# untitled.net
KiCad netlist of a schematic drawn in EAGLE
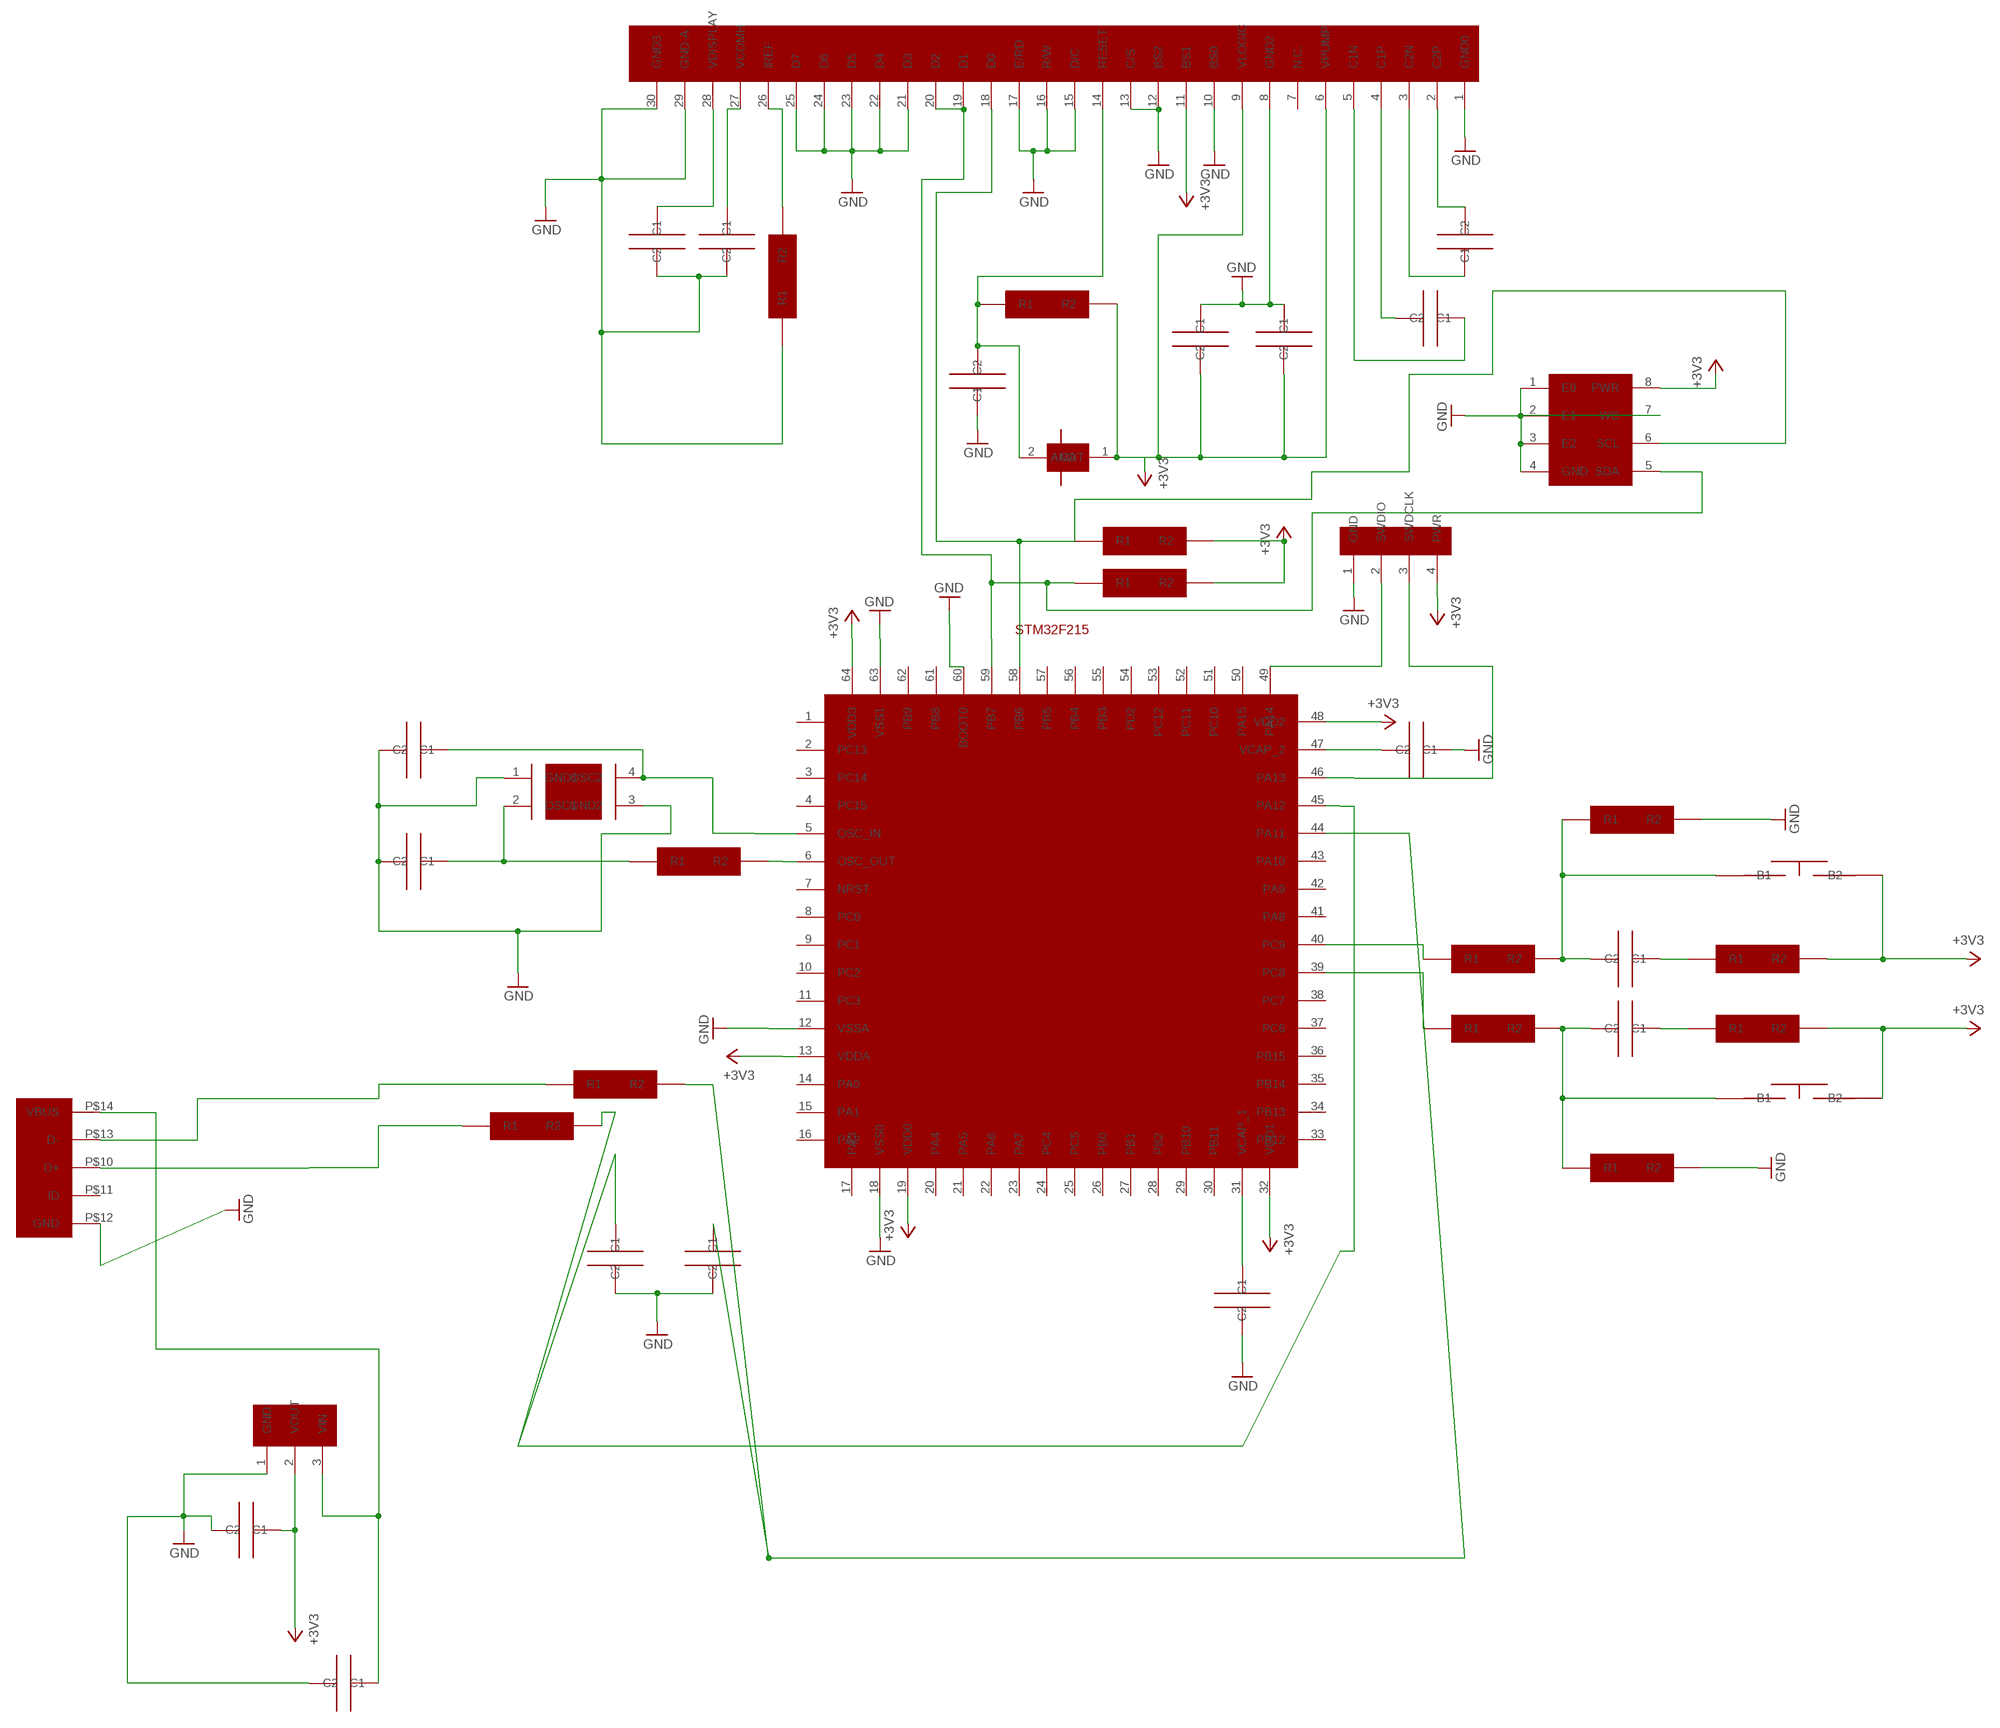
[diagram p0: schematic, sheet 1]

(export (version "E")
  (design (tool "Eeschema 10.0.6"))
  (components
    (comp (ref "C3")
      (value "10мкф")
      (footprint "eagle-import:0805")
      (libsource (lib "eagle-import") (part "C0805"))
    )
    (comp (ref "C4")
      (value "22мкф")
      (footprint "eagle-import:0805")
      (libsource (lib "eagle-import") (part "C0805"))
    )
    (comp (ref "C10")
      (value "100нф")
      (footprint "eagle-import:0805")
      (libsource (lib "eagle-import") (part "C0805"))
    )
    (comp (ref "C11")
      (value "100нф")
      (footprint "eagle-import:0805")
      (libsource (lib "eagle-import") (part "C0805"))
    )
    (comp (ref "C28")
      (value "8пф")
      (footprint "eagle-import:0805")
      (libsource (lib "eagle-import") (part "C0805"))
    )
    (comp (ref "C29")
      (value "8пф")
      (footprint "eagle-import:0805")
      (libsource (lib "eagle-import") (part "C0805"))
    )
    (comp (ref "C30")
      (value "47пф")
      (footprint "eagle-import:0805")
      (libsource (lib "eagle-import") (part "C0805"))
    )
    (comp (ref "C31")
      (value "47пф")
      (footprint "eagle-import:0805")
      (libsource (lib "eagle-import") (part "C0805"))
    )
    (comp (ref "C36")
      (value "2.2мкф")
      (footprint "eagle-import:0805")
      (libsource (lib "eagle-import") (part "C0805"))
    )
    (comp (ref "C37")
      (value "2.2мкф")
      (footprint "eagle-import:0805")
      (libsource (lib "eagle-import") (part "C0805"))
    )
    (comp (ref "C39")
      (value "1мкф")
      (footprint "eagle-import:0805")
      (libsource (lib "eagle-import") (part "C0805"))
    )
    (comp (ref "C40")
      (value "1мкф")
      (footprint "eagle-import:0805")
      (libsource (lib "eagle-import") (part "C0805"))
    )
    (comp (ref "C41")
      (value "1мкф")
      (footprint "eagle-import:0805")
      (libsource (lib "eagle-import") (part "C0805"))
    )
    (comp (ref "C42")
      (value "1мкф")
      (footprint "eagle-import:0805")
      (libsource (lib "eagle-import") (part "C0805"))
    )
    (comp (ref "C44")
      (value "4.7мкф")
      (footprint "eagle-import:0805")
      (libsource (lib "eagle-import") (part "C0805"))
    )
    (comp (ref "C46")
      (value "2.2мкф")
      (footprint "eagle-import:0805")
      (libsource (lib "eagle-import") (part "C0805"))
    )
    (comp (ref "C47")
      (value "4.7мкф")
      (footprint "eagle-import:0805")
      (libsource (lib "eagle-import") (part "C0805"))
    )
    (comp (ref "R2")
      (value "330")
      (footprint "eagle-import:0805")
      (libsource (lib "eagle-import") (part "R0805"))
    )
    (comp (ref "R3")
      (value "330")
      (footprint "eagle-import:0805")
      (libsource (lib "eagle-import") (part "R0805"))
    )
    (comp (ref "R6")
      (value "100")
      (footprint "eagle-import:0805")
      (libsource (lib "eagle-import") (part "R0805"))
    )
    (comp (ref "R7")
      (value "100")
      (footprint "eagle-import:0805")
      (libsource (lib "eagle-import") (part "R0805"))
    )
    (comp (ref "R8")
      (value "10к")
      (footprint "eagle-import:0805")
      (libsource (lib "eagle-import") (part "R0805"))
    )
    (comp (ref "R9")
      (value "10к")
      (footprint "eagle-import:0805")
      (libsource (lib "eagle-import") (part "R0805"))
    )
    (comp (ref "R14")
      (value "220k")
      (footprint "eagle-import:0805")
      (libsource (lib "eagle-import") (part "R0805"))
    )
    (comp (ref "R15")
      (value "220k")
      (footprint "eagle-import:0805")
      (libsource (lib "eagle-import") (part "R0805"))
    )
    (comp (ref "R32")
      (value "820")
      (footprint "eagle-import:0805")
      (libsource (lib "eagle-import") (part "R0805"))
    )
    (comp (ref "R33")
      (value "22")
      (footprint "eagle-import:0805")
      (libsource (lib "eagle-import") (part "R0805"))
    )
    (comp (ref "R34")
      (value "22")
      (footprint "eagle-import:0805")
      (libsource (lib "eagle-import") (part "R0805"))
    )
    (comp (ref "R43")
      (value "4.7к")
      (footprint "eagle-import:0805")
      (libsource (lib "eagle-import") (part "R0805"))
    )
    (comp (ref "R48")
      (value "910к")
      (footprint "eagle-import:0805")
      (libsource (lib "eagle-import") (part "R0805"))
    )
    (comp (ref "U$1")
      (value "STM32F215RESTM32")
      (footprint "eagle-import:QFP50P1300X1300X120-64N")
      (libsource (lib "eagle-import") (part "STM32F215RESTM32"))
    )
    (comp (ref "U$2")
      (value "AMS1117")
      (footprint "eagle-import:SOT229P729X180-4N")
      (libsource (lib "eagle-import") (part "AMS1117"))
    )
    (comp (ref "U$3")
      (value "I2CMEMORY")
      (footprint "eagle-import:SOIC127P600X175-8N")
      (libsource (lib "eagle-import") (part "I2CMEMORY"))
    )
    (comp (ref "U$4")
      (value "USBUSBT")
      (footprint "eagle-import:USBT")
      (libsource (lib "eagle-import") (part "USBUSBT"))
    )
    (comp (ref "U$5")
      (value "SWDSWDD")
      (footprint "eagle-import:HDRV4W64P254_1X4_1016X508X838B")
      (libsource (lib "eagle-import") (part "SWDSWDD"))
    )
    (comp (ref "U$18")
      (value "BUTTON")
      (footprint "eagle-import:BUTTON")
      (libsource (lib "eagle-import") (part "BUTTON"))
    )
    (comp (ref "U$19")
      (value "BUTTON")
      (footprint "eagle-import:BUTTON")
      (libsource (lib "eagle-import") (part "BUTTON"))
    )
    (comp (ref "U$26")
      (value "NX2520SA")
      (footprint "eagle-import:NX2520SA")
      (libsource (lib "eagle-import") (part "NX2520SA"))
    )
    (comp (ref "U$38")
      (value "SSD1306")
      (footprint "eagle-import:SSD1306")
      (libsource (lib "eagle-import") (part "SSD1306"))
    )
    (comp (ref "U$45")
      (value "ESD")
      (footprint "eagle-import:ESD")
      (libsource (lib "eagle-import") (part "ESD"))
    )
  )
  (nets
    (net (code "1") (name "+3V3") (class "Default")
      (node (ref "C4") (pin "2") (pinfunction "C2_2") (pintype "bidirectional"))
      (node (ref "C41") (pin "1") (pinfunction "C1_1") (pintype "bidirectional"))
      (node (ref "C42") (pin "1") (pinfunction "C1_1") (pintype "bidirectional"))
      (node (ref "R43") (pin "2") (pinfunction "R2_2") (pintype "bidirectional"))
      (node (ref "R6") (pin "2") (pinfunction "R2_2") (pintype "bidirectional"))
      (node (ref "R7") (pin "2") (pinfunction "R2_2") (pintype "bidirectional"))
      (node (ref "R8") (pin "2") (pinfunction "R2_2") (pintype "bidirectional"))
      (node (ref "R9") (pin "2") (pinfunction "R2_2") (pintype "bidirectional"))
      (node (ref "U$1") (pin "13") (pinfunction "VDDA_13") (pintype "bidirectional"))
      (node (ref "U$1") (pin "19") (pinfunction "VDD0_19") (pintype "bidirectional"))
      (node (ref "U$1") (pin "32") (pinfunction "VDD1_32") (pintype "power_in"))
      (node (ref "U$1") (pin "48") (pinfunction "VDD2_48") (pintype "bidirectional"))
      (node (ref "U$1") (pin "64") (pinfunction "VDD3_64") (pintype "bidirectional"))
      (node (ref "U$18") (pin "2") (pinfunction "B2_2") (pintype "bidirectional"))
      (node (ref "U$19") (pin "2") (pinfunction "B2_2") (pintype "bidirectional"))
      (node (ref "U$2") (pin "2") (pinfunction "VOUT_2") (pintype "bidirectional"))
      (node (ref "U$3") (pin "8") (pinfunction "PWR_8") (pintype "bidirectional"))
      (node (ref "U$38") (pin "11") (pinfunction "BS1_11") (pintype "bidirectional"))
      (node (ref "U$38") (pin "6") (pinfunction "VPUMP_6") (pintype "bidirectional"))
      (node (ref "U$38") (pin "9") (pinfunction "VLOGIC_9") (pintype "bidirectional"))
      (node (ref "U$45") (pin "1") (pinfunction "ANO_1") (pintype "bidirectional"))
      (node (ref "U$5") (pin "4") (pinfunction "PWR_4") (pintype "bidirectional"))
    )
    (net (code "2") (name "/VBAT") (class "Default")
      (node (ref "U$1") (pin "1") (pinfunction "VBAT_1") (pintype "power_in"))
    )
    (net (code "3") (name "GND") (class "Default")
      (node (ref "C28") (pin "1") (pinfunction "C1_1") (pintype "bidirectional"))
      (node (ref "C29") (pin "1") (pinfunction "C1_1") (pintype "bidirectional"))
      (node (ref "C3") (pin "1") (pinfunction "C1_1") (pintype "bidirectional"))
      (node (ref "C30") (pin "1") (pinfunction "C1_1") (pintype "bidirectional"))
      (node (ref "C31") (pin "1") (pinfunction "C1_1") (pintype "bidirectional"))
      (node (ref "C36") (pin "1") (pinfunction "C1_1") (pintype "bidirectional"))
      (node (ref "C37") (pin "2") (pinfunction "C2_2") (pintype "bidirectional"))
      (node (ref "C4") (pin "1") (pinfunction "C1_1") (pintype "bidirectional"))
      (node (ref "C41") (pin "2") (pinfunction "C2_2") (pintype "bidirectional"))
      (node (ref "C42") (pin "2") (pinfunction "C2_2") (pintype "bidirectional"))
      (node (ref "C44") (pin "2") (pinfunction "C2_2") (pintype "bidirectional"))
      (node (ref "C46") (pin "1") (pinfunction "C1_1") (pintype "bidirectional"))
      (node (ref "C47") (pin "1") (pinfunction "C1_1") (pintype "bidirectional"))
      (node (ref "R14") (pin "2") (pinfunction "R2_2") (pintype "bidirectional"))
      (node (ref "R15") (pin "2") (pinfunction "R2_2") (pintype "bidirectional"))
      (node (ref "R48") (pin "1") (pinfunction "R1_1") (pintype "bidirectional"))
      (node (ref "U$1") (pin "12") (pinfunction "VSSA_12") (pintype "bidirectional"))
      (node (ref "U$1") (pin "18") (pinfunction "VSS0_18") (pintype "bidirectional"))
      (node (ref "U$1") (pin "60") (pinfunction "BOOT0_60") (pintype "bidirectional"))
      (node (ref "U$1") (pin "63") (pinfunction "VSS1_63") (pintype "bidirectional"))
      (node (ref "U$2") (pin "1") (pinfunction "GND_1") (pintype "bidirectional"))
      (node (ref "U$26") (pin "1") (pinfunction "GND1_1") (pintype "bidirectional"))
      (node (ref "U$26") (pin "3") (pinfunction "GND2_3") (pintype "bidirectional"))
      (node (ref "U$3") (pin "1") (pinfunction "E0_1") (pintype "bidirectional"))
      (node (ref "U$3") (pin "2") (pinfunction "E1_2") (pintype "bidirectional"))
      (node (ref "U$3") (pin "3") (pinfunction "E2_3") (pintype "bidirectional"))
      (node (ref "U$3") (pin "4") (pinfunction "GND_4") (pintype "bidirectional"))
      (node (ref "U$3") (pin "7") (pinfunction "WC_7") (pintype "bidirectional"))
      (node (ref "U$38") (pin "1") (pinfunction "GND0_1") (pintype "bidirectional"))
      (node (ref "U$38") (pin "10") (pinfunction "BS0_10") (pintype "bidirectional"))
      (node (ref "U$38") (pin "12") (pinfunction "BS2_12") (pintype "bidirectional"))
      (node (ref "U$38") (pin "13") (pinfunction "C/S_13") (pintype "bidirectional"))
      (node (ref "U$38") (pin "15") (pinfunction "D/C_15") (pintype "bidirectional"))
      (node (ref "U$38") (pin "16") (pinfunction "R/W_16") (pintype "bidirectional"))
      (node (ref "U$38") (pin "17") (pinfunction "E/RD_17") (pintype "bidirectional"))
      (node (ref "U$38") (pin "21") (pinfunction "D3_21") (pintype "bidirectional"))
      (node (ref "U$38") (pin "22") (pinfunction "D4_22") (pintype "bidirectional"))
      (node (ref "U$38") (pin "23") (pinfunction "D5_23") (pintype "bidirectional"))
      (node (ref "U$38") (pin "24") (pinfunction "D6_24") (pintype "bidirectional"))
      (node (ref "U$38") (pin "25") (pinfunction "D7_25") (pintype "bidirectional"))
      (node (ref "U$38") (pin "29") (pinfunction "GND-A_29") (pintype "bidirectional"))
      (node (ref "U$38") (pin "30") (pinfunction "GND3_30") (pintype "bidirectional"))
      (node (ref "U$38") (pin "8") (pinfunction "GND2_8") (pintype "bidirectional"))
      (node (ref "U$4") (pin "P$12") (pinfunction "GND_P$12") (pintype "bidirectional"))
      (node (ref "U$5") (pin "1") (pinfunction "GND_1") (pintype "bidirectional"))
    )
    (net (code "4") (name "Net-(C3-C2)") (class "Default")
      (node (ref "C3") (pin "2") (pinfunction "C2_2") (pintype "bidirectional"))
      (node (ref "U$2") (pin "3") (pinfunction "VIN_3") (pintype "bidirectional"))
      (node (ref "U$4") (pin "P$14") (pinfunction "VBUS_P$14") (pintype "bidirectional"))
    )
    (net (code "5") (name "Net-(C10-C1)") (class "Default")
      (node (ref "C10") (pin "1") (pinfunction "C1_1") (pintype "bidirectional"))
      (node (ref "R14") (pin "1") (pinfunction "R1_1") (pintype "bidirectional"))
      (node (ref "R2") (pin "2") (pinfunction "R2_2") (pintype "bidirectional"))
      (node (ref "U$18") (pin "1") (pinfunction "B1_1") (pintype "bidirectional"))
    )
    (net (code "6") (name "Net-(C10-C2)") (class "Default")
      (node (ref "C10") (pin "2") (pinfunction "C2_2") (pintype "bidirectional"))
      (node (ref "R6") (pin "1") (pinfunction "R1_1") (pintype "bidirectional"))
    )
    (net (code "7") (name "Net-(C11-C1)") (class "Default")
      (node (ref "C11") (pin "1") (pinfunction "C1_1") (pintype "bidirectional"))
      (node (ref "R15") (pin "1") (pinfunction "R1_1") (pintype "bidirectional"))
      (node (ref "R3") (pin "2") (pinfunction "R2_2") (pintype "bidirectional"))
      (node (ref "U$19") (pin "1") (pinfunction "B1_1") (pintype "bidirectional"))
    )
    (net (code "8") (name "Net-(C11-C2)") (class "Default")
      (node (ref "C11") (pin "2") (pinfunction "C2_2") (pintype "bidirectional"))
      (node (ref "R7") (pin "1") (pinfunction "R1_1") (pintype "bidirectional"))
    )
    (net (code "9") (name "Net-(C28-C2)") (class "Default")
      (node (ref "C28") (pin "2") (pinfunction "C2_2") (pintype "bidirectional"))
      (node (ref "U$1") (pin "5") (pinfunction "OSC_IN_5") (pintype "input"))
      (node (ref "U$26") (pin "4") (pinfunction "OSC2_4") (pintype "bidirectional"))
    )
    (net (code "10") (name "Net-(C29-C2)") (class "Default")
      (node (ref "C29") (pin "2") (pinfunction "C2_2") (pintype "bidirectional"))
      (node (ref "R32") (pin "1") (pinfunction "R1_1") (pintype "bidirectional"))
      (node (ref "U$26") (pin "2") (pinfunction "OSC1_2") (pintype "bidirectional"))
    )
    (net (code "11") (name "Net-(C30-C2)") (class "Default")
      (node (ref "C30") (pin "2") (pinfunction "C2_2") (pintype "bidirectional"))
      (node (ref "R33") (pin "2") (pinfunction "R2_2") (pintype "bidirectional"))
      (node (ref "U$1") (pin "44") (pinfunction "PA11_44") (pintype "bidirectional"))
    )
    (net (code "12") (name "Net-(C31-C2)") (class "Default")
      (node (ref "C31") (pin "2") (pinfunction "C2_2") (pintype "bidirectional"))
      (node (ref "R34") (pin "2") (pinfunction "R2_2") (pintype "bidirectional"))
      (node (ref "U$1") (pin "45") (pinfunction "PA12_45") (pintype "bidirectional"))
    )
    (net (code "13") (name "Net-(C36-C2)") (class "Default")
      (node (ref "C36") (pin "2") (pinfunction "C2_2") (pintype "bidirectional"))
      (node (ref "U$1") (pin "31") (pinfunction "VCAP_1_31") (pintype "bidirectional"))
    )
    (net (code "14") (name "Net-(C37-C1)") (class "Default")
      (node (ref "C37") (pin "1") (pinfunction "C1_1") (pintype "bidirectional"))
      (node (ref "U$1") (pin "47") (pinfunction "VCAP_2_47") (pintype "bidirectional"))
    )
    (net (code "15") (name "Net-(C39-C1)") (class "Default")
      (node (ref "C39") (pin "1") (pinfunction "C1_1") (pintype "bidirectional"))
      (node (ref "U$38") (pin "2") (pinfunction "C2P_2") (pintype "bidirectional"))
    )
    (net (code "16") (name "Net-(C39-C2)") (class "Default")
      (node (ref "C39") (pin "2") (pinfunction "C2_2") (pintype "bidirectional"))
      (node (ref "U$38") (pin "3") (pinfunction "C2N_3") (pintype "bidirectional"))
    )
    (net (code "17") (name "Net-(C40-C1)") (class "Default")
      (node (ref "C40") (pin "1") (pinfunction "C1_1") (pintype "bidirectional"))
      (node (ref "U$38") (pin "4") (pinfunction "C1P_4") (pintype "bidirectional"))
    )
    (net (code "18") (name "Net-(C40-C2)") (class "Default")
      (node (ref "C40") (pin "2") (pinfunction "C2_2") (pintype "bidirectional"))
      (node (ref "U$38") (pin "5") (pinfunction "C1N_5") (pintype "bidirectional"))
    )
    (net (code "19") (name "Net-(C44-C1)") (class "Default")
      (node (ref "C44") (pin "1") (pinfunction "C1_1") (pintype "bidirectional"))
      (node (ref "R43") (pin "1") (pinfunction "R1_1") (pintype "bidirectional"))
      (node (ref "U$38") (pin "14") (pinfunction "RESET_14") (pintype "bidirectional"))
      (node (ref "U$45") (pin "2") (pinfunction "CAT_2") (pintype "bidirectional"))
    )
    (net (code "20") (name "Net-(C46-C2)") (class "Default")
      (node (ref "C46") (pin "2") (pinfunction "C2_2") (pintype "bidirectional"))
      (node (ref "U$38") (pin "28") (pinfunction "VDISPLAY_28") (pintype "bidirectional"))
    )
    (net (code "21") (name "Net-(C47-C2)") (class "Default")
      (node (ref "C47") (pin "2") (pinfunction "C2_2") (pintype "bidirectional"))
      (node (ref "U$38") (pin "27") (pinfunction "VCOMH_27") (pintype "bidirectional"))
    )
    (net (code "22") (name "Net-(R2-R1)") (class "Default")
      (node (ref "R2") (pin "1") (pinfunction "R1_1") (pintype "bidirectional"))
      (node (ref "U$1") (pin "40") (pinfunction "PC9_40") (pintype "bidirectional"))
    )
    (net (code "23") (name "Net-(R3-R1)") (class "Default")
      (node (ref "R3") (pin "1") (pinfunction "R1_1") (pintype "bidirectional"))
      (node (ref "U$1") (pin "39") (pinfunction "PC8_39") (pintype "bidirectional"))
    )
    (net (code "24") (name "Net-(R8-R1)") (class "Default")
      (node (ref "R8") (pin "1") (pinfunction "R1_1") (pintype "bidirectional"))
      (node (ref "U$1") (pin "58") (pinfunction "PB6_58") (pintype "bidirectional"))
      (node (ref "U$3") (pin "6") (pinfunction "SCL_6") (pintype "bidirectional"))
      (node (ref "U$38") (pin "18") (pinfunction "D0_18") (pintype "bidirectional"))
    )
    (net (code "25") (name "Net-(R9-R1)") (class "Default")
      (node (ref "R9") (pin "1") (pinfunction "R1_1") (pintype "bidirectional"))
      (node (ref "U$1") (pin "59") (pinfunction "PB7_59") (pintype "bidirectional"))
      (node (ref "U$3") (pin "5") (pinfunction "SDA_5") (pintype "bidirectional"))
      (node (ref "U$38") (pin "19") (pinfunction "D1_19") (pintype "bidirectional"))
      (node (ref "U$38") (pin "20") (pinfunction "D2_20") (pintype "bidirectional"))
    )
    (net (code "26") (name "Net-(R32-R2)") (class "Default")
      (node (ref "R32") (pin "2") (pinfunction "R2_2") (pintype "bidirectional"))
      (node (ref "U$1") (pin "6") (pinfunction "OSC_OUT_6") (pintype "input"))
    )
    (net (code "27") (name "Net-(R33-R1)") (class "Default")
      (node (ref "R33") (pin "1") (pinfunction "R1_1") (pintype "bidirectional"))
      (node (ref "U$4") (pin "P$13") (pinfunction "D-_P$13") (pintype "bidirectional"))
    )
    (net (code "28") (name "Net-(R34-R1)") (class "Default")
      (node (ref "R34") (pin "1") (pinfunction "R1_1") (pintype "bidirectional"))
      (node (ref "U$4") (pin "P$10") (pinfunction "D+_P$10") (pintype "bidirectional"))
    )
    (net (code "29") (name "Net-(R48-R2)") (class "Default")
      (node (ref "R48") (pin "2") (pinfunction "R2_2") (pintype "bidirectional"))
      (node (ref "U$38") (pin "26") (pinfunction "IREF_26") (pintype "bidirectional"))
    )
    (net (code "30") (name "Net-(U$1-PA13)") (class "Default")
      (node (ref "U$1") (pin "46") (pinfunction "PA13_46") (pintype "bidirectional"))
      (node (ref "U$5") (pin "3") (pinfunction "SWDCLK_3") (pintype "bidirectional"))
    )
    (net (code "31") (name "Net-(U$1-PA14)") (class "Default")
      (node (ref "U$1") (pin "49") (pinfunction "PA14_49") (pintype "bidirectional"))
      (node (ref "U$5") (pin "2") (pinfunction "SWDIO_2") (pintype "bidirectional"))
    )
    (net (code "32") (name "unconnected-(U$1-NRST-Pad7)") (class "Default")
      (node (ref "U$1") (pin "7") (pinfunction "NRST_7") (pintype "bidirectional"))
    )
    (net (code "33") (name "unconnected-(U$1-PA0-Pad14)") (class "Default")
      (node (ref "U$1") (pin "14") (pinfunction "PA0_14") (pintype "bidirectional"))
    )
    (net (code "34") (name "unconnected-(U$1-PA1-Pad15)") (class "Default")
      (node (ref "U$1") (pin "15") (pinfunction "PA1_15") (pintype "bidirectional"))
    )
    (net (code "35") (name "unconnected-(U$1-PA2-Pad16)") (class "Default")
      (node (ref "U$1") (pin "16") (pinfunction "PA2_16") (pintype "bidirectional"))
    )
    (net (code "36") (name "unconnected-(U$1-PA3-Pad17)") (class "Default")
      (node (ref "U$1") (pin "17") (pinfunction "PA3_17") (pintype "bidirectional"))
    )
    (net (code "37") (name "unconnected-(U$1-PA4-Pad20)") (class "Default")
      (node (ref "U$1") (pin "20") (pinfunction "PA4_20") (pintype "bidirectional"))
    )
    (net (code "38") (name "unconnected-(U$1-PA5-Pad21)") (class "Default")
      (node (ref "U$1") (pin "21") (pinfunction "PA5_21") (pintype "bidirectional"))
    )
    (net (code "39") (name "unconnected-(U$1-PA6-Pad22)") (class "Default")
      (node (ref "U$1") (pin "22") (pinfunction "PA6_22") (pintype "bidirectional"))
    )
    (net (code "40") (name "unconnected-(U$1-PA7-Pad23)") (class "Default")
      (node (ref "U$1") (pin "23") (pinfunction "PA7_23") (pintype "bidirectional"))
    )
    (net (code "41") (name "unconnected-(U$1-PA8-Pad41)") (class "Default")
      (node (ref "U$1") (pin "41") (pinfunction "PA8_41") (pintype "bidirectional"))
    )
    (net (code "42") (name "unconnected-(U$1-PA9-Pad42)") (class "Default")
      (node (ref "U$1") (pin "42") (pinfunction "PA9_42") (pintype "bidirectional"))
    )
    (net (code "43") (name "unconnected-(U$1-PA10-Pad43)") (class "Default")
      (node (ref "U$1") (pin "43") (pinfunction "PA10_43") (pintype "bidirectional"))
    )
    (net (code "44") (name "unconnected-(U$1-PA15-Pad50)") (class "Default")
      (node (ref "U$1") (pin "50") (pinfunction "PA15_50") (pintype "bidirectional"))
    )
    (net (code "45") (name "unconnected-(U$1-PB0-Pad26)") (class "Default")
      (node (ref "U$1") (pin "26") (pinfunction "PB0_26") (pintype "bidirectional"))
    )
    (net (code "46") (name "unconnected-(U$1-PB1-Pad27)") (class "Default")
      (node (ref "U$1") (pin "27") (pinfunction "PB1_27") (pintype "bidirectional"))
    )
    (net (code "47") (name "unconnected-(U$1-PB2-Pad28)") (class "Default")
      (node (ref "U$1") (pin "28") (pinfunction "PB2_28") (pintype "bidirectional"))
    )
    (net (code "48") (name "unconnected-(U$1-PB3-Pad55)") (class "Default")
      (node (ref "U$1") (pin "55") (pinfunction "PB3_55") (pintype "bidirectional"))
    )
    (net (code "49") (name "unconnected-(U$1-PB4-Pad56)") (class "Default")
      (node (ref "U$1") (pin "56") (pinfunction "PB4_56") (pintype "bidirectional"))
    )
    (net (code "50") (name "unconnected-(U$1-PB5-Pad57)") (class "Default")
      (node (ref "U$1") (pin "57") (pinfunction "PB5_57") (pintype "bidirectional"))
    )
    (net (code "51") (name "unconnected-(U$1-PB8-Pad61)") (class "Default")
      (node (ref "U$1") (pin "61") (pinfunction "PB8_61") (pintype "bidirectional"))
    )
    (net (code "52") (name "unconnected-(U$1-PB9-Pad62)") (class "Default")
      (node (ref "U$1") (pin "62") (pinfunction "PB9_62") (pintype "bidirectional"))
    )
    (net (code "53") (name "unconnected-(U$1-PB10-Pad29)") (class "Default")
      (node (ref "U$1") (pin "29") (pinfunction "PB10_29") (pintype "bidirectional"))
    )
    (net (code "54") (name "unconnected-(U$1-PB11-Pad30)") (class "Default")
      (node (ref "U$1") (pin "30") (pinfunction "PB11_30") (pintype "bidirectional"))
    )
    (net (code "55") (name "unconnected-(U$1-PB12-Pad33)") (class "Default")
      (node (ref "U$1") (pin "33") (pinfunction "PB12_33") (pintype "bidirectional"))
    )
    (net (code "56") (name "unconnected-(U$1-PB13-Pad34)") (class "Default")
      (node (ref "U$1") (pin "34") (pinfunction "PB13_34") (pintype "bidirectional"))
    )
    (net (code "57") (name "unconnected-(U$1-PB14-Pad35)") (class "Default")
      (node (ref "U$1") (pin "35") (pinfunction "PB14_35") (pintype "bidirectional"))
    )
    (net (code "58") (name "unconnected-(U$1-PB15-Pad36)") (class "Default")
      (node (ref "U$1") (pin "36") (pinfunction "PB15_36") (pintype "bidirectional"))
    )
    (net (code "59") (name "unconnected-(U$1-PC0-Pad8)") (class "Default")
      (node (ref "U$1") (pin "8") (pinfunction "PC0_8") (pintype "bidirectional"))
    )
    (net (code "60") (name "unconnected-(U$1-PC1-Pad9)") (class "Default")
      (node (ref "U$1") (pin "9") (pinfunction "PC1_9") (pintype "bidirectional"))
    )
    (net (code "61") (name "unconnected-(U$1-PC2-Pad10)") (class "Default")
      (node (ref "U$1") (pin "10") (pinfunction "PC2_10") (pintype "bidirectional"))
    )
    (net (code "62") (name "unconnected-(U$1-PC3-Pad11)") (class "Default")
      (node (ref "U$1") (pin "11") (pinfunction "PC3_11") (pintype "bidirectional"))
    )
    (net (code "63") (name "unconnected-(U$1-PC4-Pad24)") (class "Default")
      (node (ref "U$1") (pin "24") (pinfunction "PC4_24") (pintype "bidirectional"))
    )
    (net (code "64") (name "unconnected-(U$1-PC5-Pad25)") (class "Default")
      (node (ref "U$1") (pin "25") (pinfunction "PC5_25") (pintype "bidirectional"))
    )
    (net (code "65") (name "unconnected-(U$1-PC6-Pad37)") (class "Default")
      (node (ref "U$1") (pin "37") (pinfunction "PC6_37") (pintype "bidirectional"))
    )
    (net (code "66") (name "unconnected-(U$1-PC7-Pad38)") (class "Default")
      (node (ref "U$1") (pin "38") (pinfunction "PC7_38") (pintype "bidirectional"))
    )
    (net (code "67") (name "unconnected-(U$1-PC10-Pad51)") (class "Default")
      (node (ref "U$1") (pin "51") (pinfunction "PC10_51") (pintype "bidirectional"))
    )
    (net (code "68") (name "unconnected-(U$1-PC11-Pad52)") (class "Default")
      (node (ref "U$1") (pin "52") (pinfunction "PC11_52") (pintype "bidirectional"))
    )
    (net (code "69") (name "unconnected-(U$1-PC12-Pad53)") (class "Default")
      (node (ref "U$1") (pin "53") (pinfunction "PC12_53") (pintype "bidirectional"))
    )
    (net (code "70") (name "unconnected-(U$1-PC13-Pad2)") (class "Default")
      (node (ref "U$1") (pin "2") (pinfunction "PC13_2") (pintype "bidirectional"))
    )
    (net (code "71") (name "unconnected-(U$1-PC14-Pad3)") (class "Default")
      (node (ref "U$1") (pin "3") (pinfunction "PC14_3") (pintype "bidirectional"))
    )
    (net (code "72") (name "unconnected-(U$1-PC15-Pad4)") (class "Default")
      (node (ref "U$1") (pin "4") (pinfunction "PC15_4") (pintype "bidirectional"))
    )
    (net (code "73") (name "unconnected-(U$1-PD2-Pad54)") (class "Default")
      (node (ref "U$1") (pin "54") (pinfunction "PD2_54") (pintype "bidirectional"))
    )
    (net (code "74") (name "unconnected-(U$4-ID-PadP$11)") (class "Default")
      (node (ref "U$4") (pin "P$11") (pinfunction "ID_P$11") (pintype "bidirectional"))
    )
    (net (code "75") (name "unconnected-(U$38-N.C.-Pad7)") (class "Default")
      (node (ref "U$38") (pin "7") (pinfunction "N.C._7") (pintype "bidirectional"))
    )
  )
)
